# unicorder-mk-2_1.net
KiCad netlist of a schematic drawn in EAGLE
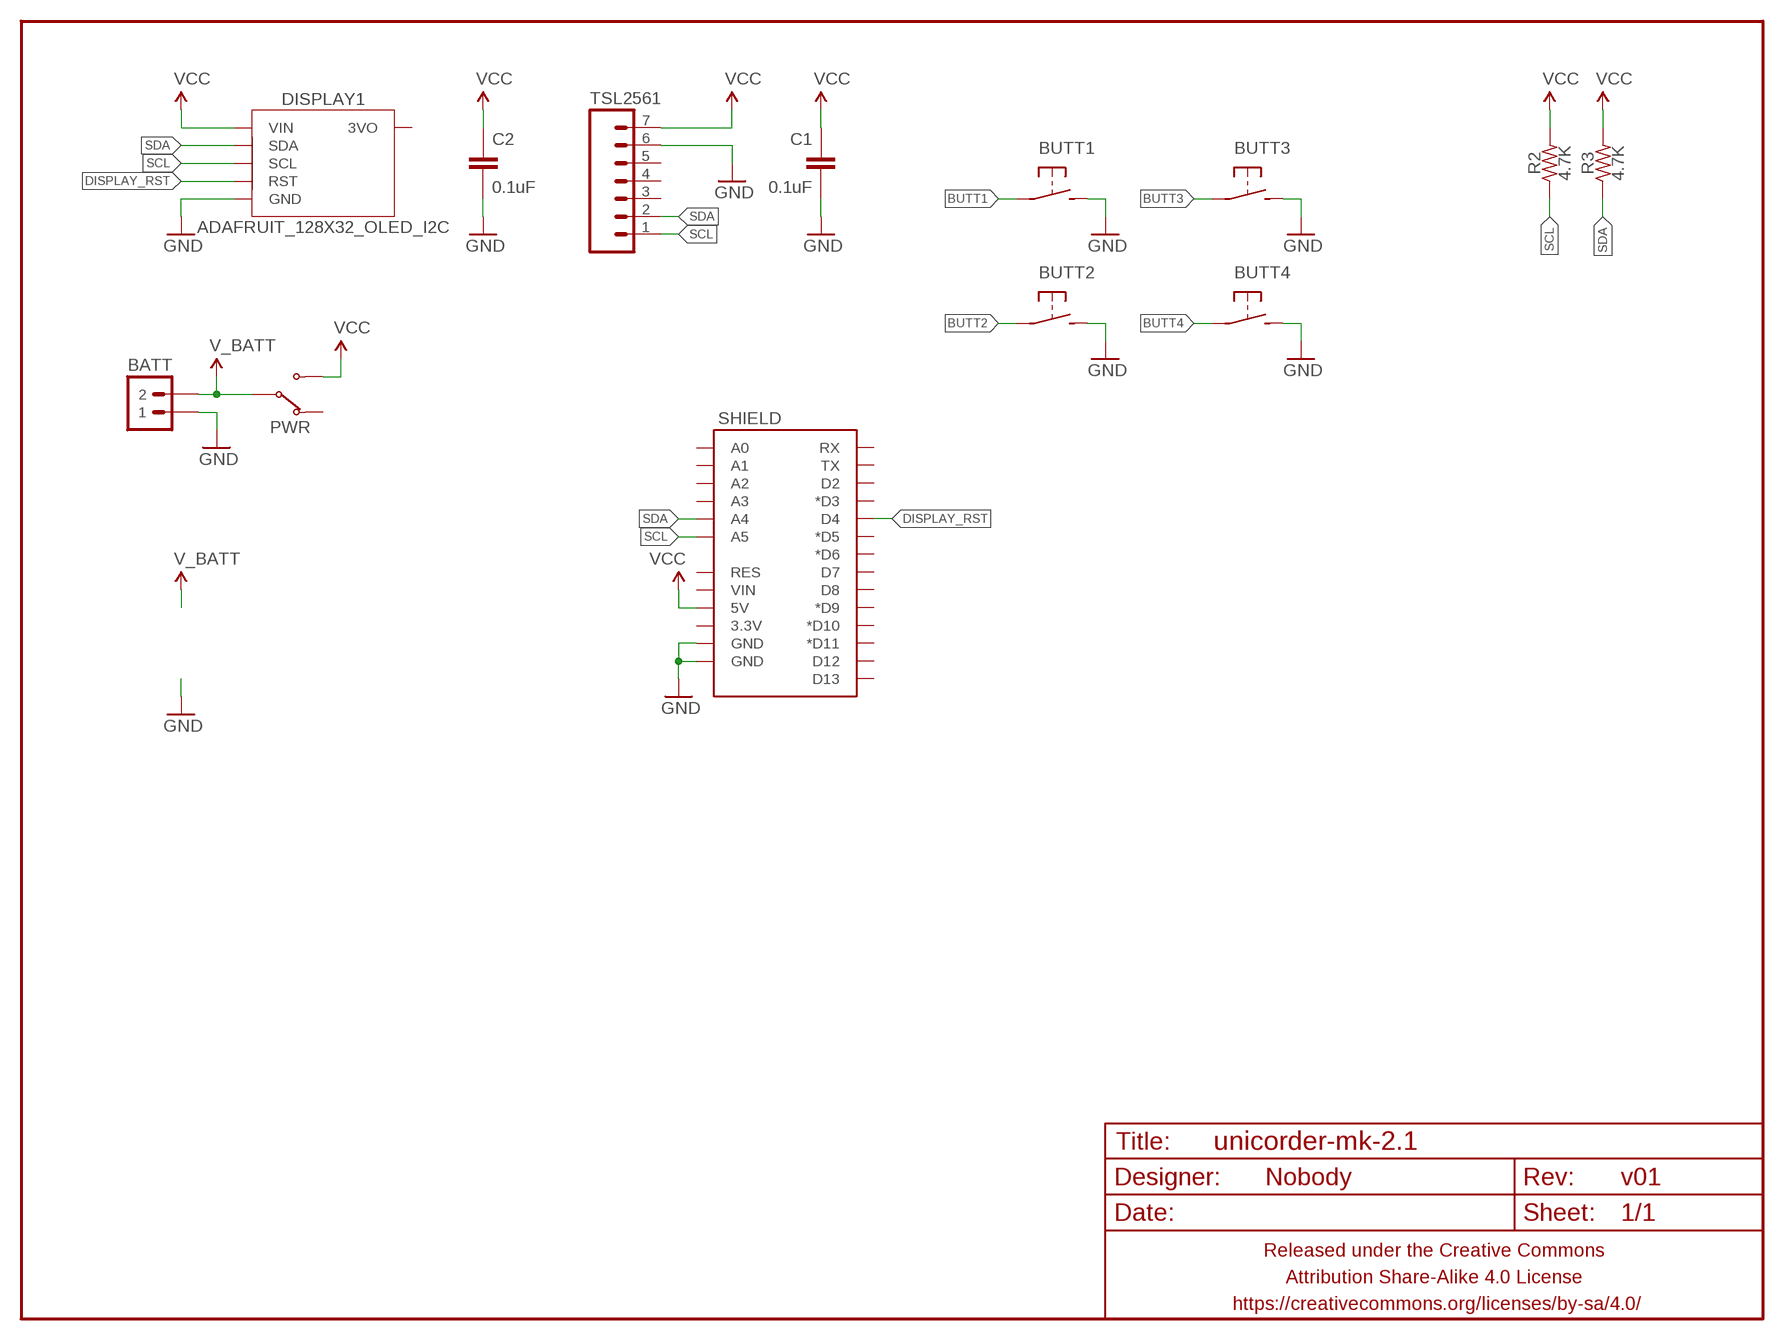
[diagram p0: schematic, sheet 1]

(export (version "E")
  (design (tool "Eeschema 10.0.6"))
  (components
    (comp (ref "BATT")
      (value "M02JST-PTH-VERT")
      (footprint "eagle-import:JST-2-PH-VERT-PTH")
      (libsource (lib "eagle-import") (part "M02JST-PTH-VERT"))
    )
    (comp (ref "BUTT1")
      (value "SPST-NO-TACT6MM-PTH-SMALL-PADS")
      (footprint "eagle-import:DTS-6-SMALL-PADS")
      (libsource (lib "eagle-import") (part "SPST-NO-TACT6MM-PTH-SMALL-PADS"))
    )
    (comp (ref "BUTT2")
      (value "SPST-NO-TACT6MM-PTH-SMALL-PADS")
      (footprint "eagle-import:DTS-6-SMALL-PADS")
      (libsource (lib "eagle-import") (part "SPST-NO-TACT6MM-PTH-SMALL-PADS"))
    )
    (comp (ref "BUTT3")
      (value "SPST-NO-TACT6MM-PTH-SMALL-PADS")
      (footprint "eagle-import:DTS-6-SMALL-PADS")
      (libsource (lib "eagle-import") (part "SPST-NO-TACT6MM-PTH-SMALL-PADS"))
    )
    (comp (ref "BUTT4")
      (value "SPST-NO-TACT6MM-PTH-SMALL-PADS")
      (footprint "eagle-import:DTS-6-SMALL-PADS")
      (libsource (lib "eagle-import") (part "SPST-NO-TACT6MM-PTH-SMALL-PADS"))
    )
    (comp (ref "C1")
      (value "0.1uF")
      (footprint "eagle-import:C025-024X044")
      (libsource (lib "eagle-import") (part "CAPACITOR-CERAMIC025-024X044"))
    )
    (comp (ref "C2")
      (value "0.1uF")
      (footprint "eagle-import:C025-024X044")
      (libsource (lib "eagle-import") (part "CAPACITOR-CERAMIC025-024X044"))
    )
    (comp (ref "DISPLAY1")
      (value "ADAFRUIT_128X32_OLED_I2C")
      (footprint "eagle-import:ADAFRUIT_128X32_OLED_I2C_CLOSER")
      (libsource (lib "eagle-import") (part "ADAFRUIT_128X32_OLED_I2CCLOSER"))
    )
    (comp (ref "FRAME1")
      (value "FRAME-LETTERNO_PACKAGE")
      (footprint "eagle-import:DUMMY")
      (fields (field (name "DESIGNER") "Nobody"))
      (libsource (lib "eagle-import") (part "FRAME-LETTERNO_PACKAGE"))
    )
    (comp (ref "PWR")
      (value "SWITCH-SPDTPTH-VERT-2.54MM")
      (footprint "eagle-import:SWITCH-SPDT")
      (libsource (lib "eagle-import") (part "SWITCH-SPDTPTH-VERT-2.54MM"))
    )
    (comp (ref "R2")
      (value "4.7K")
      (footprint "eagle-import:RESISTOR-AXIAL-PTH-6.35MM")
      (libsource (lib "eagle-import") (part "RESISTORPTH-AXIAL-6.35MM"))
    )
    (comp (ref "R3")
      (value "4.7K")
      (footprint "eagle-import:RESISTOR-AXIAL-PTH-6.35MM")
      (libsource (lib "eagle-import") (part "RESISTORPTH-AXIAL-6.35MM"))
    )
    (comp (ref "SHIELD")
      (value "ARDUINO_SHIELD_SMALLER")
      (footprint "eagle-import:ARDUINO_SHIELD_NOOUTLINE_INSIDE_SMALLER")
      (libsource (lib "eagle-import") (part "ARDUINO_SHIELD_SMALLER"))
    )
    (comp (ref "TSL2561")
      (value "M07PTH-SLIMASS")
      (footprint "eagle-import:1X07_PTH_SLIMASS")
      (libsource (lib "eagle-import") (part "M07PTH-SLIMASS"))
    )
  )
  (nets
    (net (code "1") (name "BUTT1") (class "Default")
      (node (ref "BUTT1") (pin "1") (pinfunction "1_1") (pintype "passive"))
      (node (ref "BUTT1") (pin "2") (pinfunction "1_2") (pintype "passive"))
    )
    (net (code "2") (name "BUTT2") (class "Default")
      (node (ref "BUTT2") (pin "1") (pinfunction "1_1") (pintype "passive"))
      (node (ref "BUTT2") (pin "2") (pinfunction "1_2") (pintype "passive"))
    )
    (net (code "3") (name "BUTT3") (class "Default")
      (node (ref "BUTT3") (pin "1") (pinfunction "1_1") (pintype "passive"))
      (node (ref "BUTT3") (pin "2") (pinfunction "1_2") (pintype "passive"))
    )
    (net (code "4") (name "BUTT4") (class "Default")
      (node (ref "BUTT4") (pin "1") (pinfunction "1_1") (pintype "passive"))
      (node (ref "BUTT4") (pin "2") (pinfunction "1_2") (pintype "passive"))
    )
    (net (code "5") (name "DISPLAY_RST") (class "Default")
      (node (ref "DISPLAY1") (pin "RST") (pinfunction "RST_RST") (pintype "bidirectional"))
      (node (ref "SHIELD") (pin "D4") (pinfunction "D4_D4") (pintype "bidirectional"))
    )
    (net (code "6") (name "GND") (class "Default")
      (node (ref "BATT") (pin "1") (pinfunction "1_1") (pintype "passive"))
      (node (ref "BUTT1") (pin "3") (pinfunction "2_3") (pintype "passive"))
      (node (ref "BUTT1") (pin "4") (pinfunction "2_4") (pintype "passive"))
      (node (ref "BUTT2") (pin "3") (pinfunction "2_3") (pintype "passive"))
      (node (ref "BUTT2") (pin "4") (pinfunction "2_4") (pintype "passive"))
      (node (ref "BUTT3") (pin "3") (pinfunction "2_3") (pintype "passive"))
      (node (ref "BUTT3") (pin "4") (pinfunction "2_4") (pintype "passive"))
      (node (ref "BUTT4") (pin "3") (pinfunction "2_3") (pintype "passive"))
      (node (ref "BUTT4") (pin "4") (pinfunction "2_4") (pintype "passive"))
      (node (ref "C1") (pin "2") (pinfunction "2_2") (pintype "passive"))
      (node (ref "C2") (pin "2") (pinfunction "2_2") (pintype "passive"))
      (node (ref "DISPLAY1") (pin "GND") (pinfunction "GND_GND") (pintype "bidirectional"))
      (node (ref "SHIELD") (pin "GND@0") (pinfunction "GND_GND@0") (pintype "bidirectional"))
      (node (ref "SHIELD") (pin "GND@1") (pinfunction "GND_GND@1") (pintype "bidirectional"))
      (node (ref "TSL2561") (pin "6") (pinfunction "6_6") (pintype "passive"))
    )
    (net (code "7") (name "SCL") (class "Default")
      (node (ref "DISPLAY1") (pin "SCL") (pinfunction "SCL_SCL") (pintype "bidirectional"))
      (node (ref "R2") (pin "P$1") (pinfunction "1_P$1") (pintype "passive"))
      (node (ref "SHIELD") (pin "A5") (pinfunction "A5_A5") (pintype "bidirectional"))
      (node (ref "TSL2561") (pin "1") (pinfunction "1_1") (pintype "passive"))
    )
    (net (code "8") (name "SDA") (class "Default")
      (node (ref "DISPLAY1") (pin "SDA") (pinfunction "SDA_SDA") (pintype "bidirectional"))
      (node (ref "R3") (pin "P$1") (pinfunction "1_P$1") (pintype "passive"))
      (node (ref "SHIELD") (pin "A4") (pinfunction "A4_A4") (pintype "bidirectional"))
      (node (ref "TSL2561") (pin "2") (pinfunction "2_2") (pintype "passive"))
    )
    (net (code "9") (name "VCC") (class "Default")
      (node (ref "C1") (pin "1") (pinfunction "1_1") (pintype "passive"))
      (node (ref "C2") (pin "1") (pinfunction "1_1") (pintype "passive"))
      (node (ref "DISPLAY1") (pin "VIN") (pinfunction "VIN_VIN") (pintype "bidirectional"))
      (node (ref "PWR") (pin "3") (pinfunction "NO_3") (pintype "passive"))
      (node (ref "R2") (pin "P$2") (pinfunction "2_P$2") (pintype "passive"))
      (node (ref "R3") (pin "P$2") (pinfunction "2_P$2") (pintype "passive"))
      (node (ref "SHIELD") (pin "5V") (pinfunction "5V_5V") (pintype "bidirectional"))
      (node (ref "TSL2561") (pin "7") (pinfunction "7_7") (pintype "passive"))
    )
    (net (code "10") (name "V_BATT") (class "Default")
      (node (ref "BATT") (pin "2") (pinfunction "2_2") (pintype "passive"))
      (node (ref "PWR") (pin "2") (pinfunction "COM_2") (pintype "passive"))
    )
    (net (code "11") (name "unconnected-(DISPLAY1-Pad3VO)") (class "Default")
      (node (ref "DISPLAY1") (pin "3VO") (pinfunction "3VO_3VO") (pintype "bidirectional"))
    )
    (net (code "12") (name "unconnected-(PWR-NC-Pad1)") (class "Default")
      (node (ref "PWR") (pin "1") (pinfunction "NC_1") (pintype "passive"))
    )
    (net (code "13") (name "unconnected-(SHIELD-*D3-PadD3)") (class "Default")
      (node (ref "SHIELD") (pin "D3") (pinfunction "*D3_D3") (pintype "bidirectional"))
    )
    (net (code "14") (name "unconnected-(SHIELD-*D5-PadD5)") (class "Default")
      (node (ref "SHIELD") (pin "D5") (pinfunction "*D5_D5") (pintype "bidirectional"))
    )
    (net (code "15") (name "unconnected-(SHIELD-*D6-PadD6)") (class "Default")
      (node (ref "SHIELD") (pin "D6") (pinfunction "*D6_D6") (pintype "bidirectional"))
    )
    (net (code "16") (name "unconnected-(SHIELD-*D9-PadD9)") (class "Default")
      (node (ref "SHIELD") (pin "D9") (pinfunction "*D9_D9") (pintype "bidirectional"))
    )
    (net (code "17") (name "unconnected-(SHIELD-*D10-PadD10)") (class "Default")
      (node (ref "SHIELD") (pin "D10") (pinfunction "*D10_D10") (pintype "bidirectional"))
    )
    (net (code "18") (name "unconnected-(SHIELD-*D11-PadD11)") (class "Default")
      (node (ref "SHIELD") (pin "D11") (pinfunction "*D11_D11") (pintype "bidirectional"))
    )
    (net (code "19") (name "unconnected-(SHIELD-Pad3.3V)") (class "Default")
      (node (ref "SHIELD") (pin "3.3V") (pinfunction "3.3V_3.3V") (pintype "bidirectional"))
    )
    (net (code "20") (name "unconnected-(SHIELD-PadA0)") (class "Default")
      (node (ref "SHIELD") (pin "A0") (pinfunction "A0_A0") (pintype "bidirectional"))
    )
    (net (code "21") (name "unconnected-(SHIELD-PadA1)") (class "Default")
      (node (ref "SHIELD") (pin "A1") (pinfunction "A1_A1") (pintype "bidirectional"))
    )
    (net (code "22") (name "unconnected-(SHIELD-PadA2)") (class "Default")
      (node (ref "SHIELD") (pin "A2") (pinfunction "A2_A2") (pintype "bidirectional"))
    )
    (net (code "23") (name "unconnected-(SHIELD-PadA3)") (class "Default")
      (node (ref "SHIELD") (pin "A3") (pinfunction "A3_A3") (pintype "bidirectional"))
    )
    (net (code "24") (name "unconnected-(SHIELD-PadD2)") (class "Default")
      (node (ref "SHIELD") (pin "D2") (pinfunction "D2_D2") (pintype "bidirectional"))
    )
    (net (code "25") (name "unconnected-(SHIELD-PadD7)") (class "Default")
      (node (ref "SHIELD") (pin "D7") (pinfunction "D7_D7") (pintype "bidirectional"))
    )
    (net (code "26") (name "unconnected-(SHIELD-PadD8)") (class "Default")
      (node (ref "SHIELD") (pin "D8") (pinfunction "D8_D8") (pintype "bidirectional"))
    )
    (net (code "27") (name "unconnected-(SHIELD-PadD12)") (class "Default")
      (node (ref "SHIELD") (pin "D12") (pinfunction "D12_D12") (pintype "bidirectional"))
    )
    (net (code "28") (name "unconnected-(SHIELD-PadD13)") (class "Default")
      (node (ref "SHIELD") (pin "D13") (pinfunction "D13_D13") (pintype "bidirectional"))
    )
    (net (code "29") (name "unconnected-(SHIELD-PadRES)") (class "Default")
      (node (ref "SHIELD") (pin "RES") (pinfunction "RES_RES") (pintype "bidirectional"))
    )
    (net (code "30") (name "unconnected-(SHIELD-PadRX)") (class "Default")
      (node (ref "SHIELD") (pin "RX") (pinfunction "RX_RX") (pintype "bidirectional"))
    )
    (net (code "31") (name "unconnected-(SHIELD-PadTX)") (class "Default")
      (node (ref "SHIELD") (pin "TX") (pinfunction "TX_TX") (pintype "bidirectional"))
    )
    (net (code "32") (name "unconnected-(SHIELD-PadVIN)") (class "Default")
      (node (ref "SHIELD") (pin "VIN") (pinfunction "VIN_VIN") (pintype "bidirectional"))
    )
    (net (code "33") (name "unconnected-(TSL2561-Pad3)") (class "Default")
      (node (ref "TSL2561") (pin "3") (pinfunction "3_3") (pintype "passive"))
    )
    (net (code "34") (name "unconnected-(TSL2561-Pad4)") (class "Default")
      (node (ref "TSL2561") (pin "4") (pinfunction "4_4") (pintype "passive"))
    )
    (net (code "35") (name "unconnected-(TSL2561-Pad5)") (class "Default")
      (node (ref "TSL2561") (pin "5") (pinfunction "5_5") (pintype "passive"))
    )
  )
)
